# PCB_ManufactureDiagram.net
KiCad netlist of a schematic drawn in Altium Designer
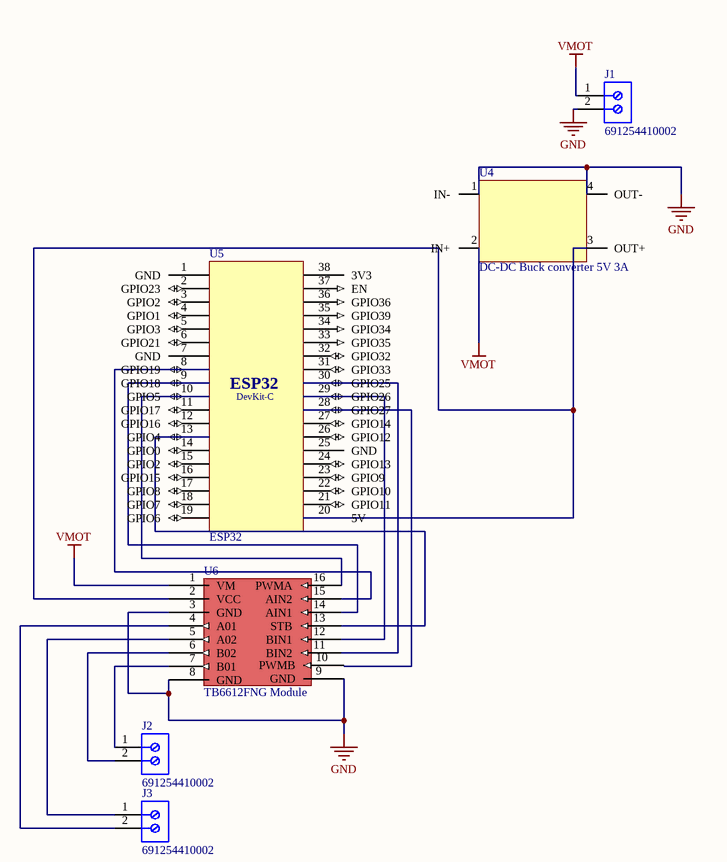
[diagram p0: PCB_ManufactureDiagram.SchDoc]

(export (version "E")
  (design (tool "Eeschema 10.0.6"))
  (components
    (comp (ref "J1")
      (value "691254410002")
      (footprint "691254410002")
      (description "Terminal Block, 7.62MM Pitch, Horizontal, Dual Pin, 12-30 AWG, 2 Pin")
      (libsource (lib "Altium Content Vault") (part "TBL - 1R - 02P - Screw"))
    )
    (comp (ref "J2")
      (value "691254410002")
      (footprint "691254410002")
      (description "Terminal Block, 7.62MM Pitch, Horizontal, Dual Pin, 12-30 AWG, 2 Pin")
      (libsource (lib "Altium Content Vault") (part "TBL - 1R - 02P - Screw"))
    )
    (comp (ref "J3")
      (value "691254410002")
      (footprint "691254410002")
      (description "Terminal Block, 7.62MM Pitch, Horizontal, Dual Pin, 12-30 AWG, 2 Pin")
      (libsource (lib "Altium Content Vault") (part "TBL - 1R - 02P - Screw"))
    )
    (comp (ref "U4")
      (value "DC-DC Buck converter 5V 3A")
      (footprint "DC-DC Buck converter 5V 3A")
      (description "MP1584 Series 28 V 3 A 1.5 MHz SMT Step-Down Converter - SOIC-8E")
      (fields
        (field (name "MANUFACTURER") "Monolithic Power Systems")
        (field (name "MANUFACTURER PART NUMBER") "MP1584EN-LF-Z")
      )
      (libsource (lib "DigiKey") (part "DC-DC Buck converter 5V 3A"))
    )
    (comp (ref "U5")
      (value "ESP32")
      (footprint "ESP32_DevKitCWROOM32")
      (description "Multiprotocol Modules SMD Module ESP32-WROOM-32E, ESP32-D0WD-V3, 16 MB SPI flash, PCB antenna")
      (fields
        (field (name "MANUFACTURER") "Espressif Systems")
        (field (name "MANUFACTURER PART NUMBER") "ESP32-WROOM-32E-N16")
      )
      (libsource (lib "EspressifSystems") (part "ESP32-WROOM32"))
    )
    (comp (ref "U6")
      (value "TB6612FNG Module")
      (footprint "TB6612FNG")
      (description "TB6612FNG Motion Motor Control Add-On Board")
      (fields (field (name "MANUFACTURER") "SparkFun") (field (name "MANUFACTURER PART NUMBER") "ROB-14451"))
      (libsource (lib "SparkfunElectronics") (part "TB6612FNG"))
    )
  )
  (nets
    (net (code "1") (name "GND") (class "Default")
      (node (ref "J1") (pin "2") (pinfunction "2_2") (pintype "passive"))
      (node (ref "U4") (pin "1") (pinfunction "IN-_1") (pintype "power_in"))
      (node (ref "U4") (pin "4") (pinfunction "OUT-_4") (pintype "power_in"))
      (node (ref "U6") (pin "3") (pinfunction "GND_3") (pintype "power_in"))
      (node (ref "U6") (pin "8") (pinfunction "GND_8") (pintype "power_in"))
      (node (ref "U6") (pin "9") (pinfunction "GND_9") (pintype "power_in"))
    )
    (net (code "2") (name "Net-(U4-OUT+)") (class "Default")
      (node (ref "U4") (pin "3") (pinfunction "OUT+_3") (pintype "power_in"))
      (node (ref "U5") (pin "20") (pinfunction "5V_20") (pintype "power_in"))
      (node (ref "U6") (pin "2") (pinfunction "VCC_2") (pintype "power_in"))
    )
    (net (code "3") (name "Net-(U5-GPIO4)") (class "Default")
      (node (ref "U5") (pin "13") (pinfunction "GPIO4_13") (pintype "bidirectional"))
      (node (ref "U6") (pin "13") (pinfunction "STB_13") (pintype "input"))
    )
    (net (code "4") (name "Net-(U5-GPIO5)") (class "Default")
      (node (ref "U5") (pin "10") (pinfunction "GPIO5_10") (pintype "bidirectional"))
      (node (ref "U6") (pin "16") (pinfunction "PWMA_16") (pintype "input"))
    )
    (net (code "5") (name "Net-(U5-GPIO18)") (class "Default")
      (node (ref "U5") (pin "9") (pinfunction "GPIO18_9") (pintype "bidirectional"))
      (node (ref "U6") (pin "14") (pinfunction "AIN1_14") (pintype "input"))
    )
    (net (code "6") (name "Net-(U5-GPIO19)") (class "Default")
      (node (ref "U5") (pin "8") (pinfunction "GPIO19_8") (pintype "bidirectional"))
      (node (ref "U6") (pin "15") (pinfunction "AIN2_15") (pintype "input"))
    )
    (net (code "7") (name "Net-(U5-GPIO25)") (class "Default")
      (node (ref "U5") (pin "30") (pinfunction "GPIO25_30") (pintype "bidirectional"))
      (node (ref "U6") (pin "11") (pinfunction "BIN2_11") (pintype "input"))
    )
    (net (code "8") (name "Net-(U5-GPIO26)") (class "Default")
      (node (ref "U5") (pin "29") (pinfunction "GPIO26_29") (pintype "bidirectional"))
      (node (ref "U6") (pin "12") (pinfunction "BIN1_12") (pintype "input"))
    )
    (net (code "9") (name "Net-(U6-A01)") (class "Default")
      (node (ref "J3") (pin "2") (pinfunction "2_2") (pintype "passive"))
      (node (ref "U6") (pin "4") (pinfunction "A01_4") (pintype "output"))
    )
    (net (code "10") (name "Net-(U6-A02)") (class "Default")
      (node (ref "J3") (pin "1") (pinfunction "1_1") (pintype "passive"))
      (node (ref "U6") (pin "5") (pinfunction "A02_5") (pintype "output"))
    )
    (net (code "11") (name "Net-(U6-B01)") (class "Default")
      (node (ref "J2") (pin "1") (pinfunction "1_1") (pintype "passive"))
      (node (ref "U6") (pin "7") (pinfunction "B01_7") (pintype "output"))
    )
    (net (code "12") (name "Net-(U6-B02)") (class "Default")
      (node (ref "J2") (pin "2") (pinfunction "2_2") (pintype "passive"))
      (node (ref "U6") (pin "6") (pinfunction "B02_6") (pintype "output"))
    )
    (net (code "13") (name "VMOT") (class "Default")
      (node (ref "J1") (pin "1") (pinfunction "1_1") (pintype "passive"))
      (node (ref "U4") (pin "2") (pinfunction "IN+_2") (pintype "power_in"))
      (node (ref "U6") (pin "1") (pinfunction "VM_1") (pintype "power_in"))
    )
    (net (code "14") (name "unconnected-(U5-3V3-Pad38)") (class "Default")
      (node (ref "U5") (pin "38") (pinfunction "3V3_38") (pintype "power_in"))
    )
    (net (code "15") (name "unconnected-(U5-EN-Pad37)") (class "Default")
      (node (ref "U5") (pin "37") (pinfunction "EN_37") (pintype "input"))
    )
    (net (code "16") (name "unconnected-(U5-GND-Pad1)") (class "Default")
      (node (ref "U5") (pin "1") (pinfunction "GND_1") (pintype "power_in"))
    )
    (net (code "17") (name "unconnected-(U5-GND-Pad7)") (class "Default")
      (node (ref "U5") (pin "7") (pinfunction "GND_7") (pintype "power_in"))
    )
    (net (code "18") (name "unconnected-(U5-GND-Pad25)") (class "Default")
      (node (ref "U5") (pin "25") (pinfunction "GND_25") (pintype "power_in"))
    )
    (net (code "19") (name "unconnected-(U5-GPIO0-Pad14)") (class "Default")
      (node (ref "U5") (pin "14") (pinfunction "GPIO0_14") (pintype "bidirectional"))
    )
    (net (code "20") (name "unconnected-(U5-GPIO1-Pad4)") (class "Default")
      (node (ref "U5") (pin "4") (pinfunction "GPIO1_4") (pintype "bidirectional"))
    )
    (net (code "21") (name "unconnected-(U5-GPIO2-Pad3)") (class "Default")
      (node (ref "U5") (pin "3") (pinfunction "GPIO2_3") (pintype "bidirectional"))
    )
    (net (code "22") (name "unconnected-(U5-GPIO2-Pad15)") (class "Default")
      (node (ref "U5") (pin "15") (pinfunction "GPIO2_15") (pintype "bidirectional"))
    )
    (net (code "23") (name "unconnected-(U5-GPIO3-Pad5)") (class "Default")
      (node (ref "U5") (pin "5") (pinfunction "GPIO3_5") (pintype "bidirectional"))
    )
    (net (code "24") (name "unconnected-(U5-GPIO6-Pad19)") (class "Default")
      (node (ref "U5") (pin "19") (pinfunction "GPIO6_19") (pintype "bidirectional"))
    )
    (net (code "25") (name "unconnected-(U5-GPIO7-Pad18)") (class "Default")
      (node (ref "U5") (pin "18") (pinfunction "GPIO7_18") (pintype "bidirectional"))
    )
    (net (code "26") (name "unconnected-(U5-GPIO8-Pad17)") (class "Default")
      (node (ref "U5") (pin "17") (pinfunction "GPIO8_17") (pintype "bidirectional"))
    )
    (net (code "27") (name "unconnected-(U5-GPIO9-Pad23)") (class "Default")
      (node (ref "U5") (pin "23") (pinfunction "GPIO9_23") (pintype "bidirectional"))
    )
    (net (code "28") (name "unconnected-(U5-GPIO10-Pad22)") (class "Default")
      (node (ref "U5") (pin "22") (pinfunction "GPIO10_22") (pintype "bidirectional"))
    )
    (net (code "29") (name "unconnected-(U5-GPIO11-Pad21)") (class "Default")
      (node (ref "U5") (pin "21") (pinfunction "GPIO11_21") (pintype "bidirectional"))
    )
    (net (code "30") (name "unconnected-(U5-GPIO12-Pad26)") (class "Default")
      (node (ref "U5") (pin "26") (pinfunction "GPIO12_26") (pintype "bidirectional"))
    )
    (net (code "31") (name "unconnected-(U5-GPIO13-Pad24)") (class "Default")
      (node (ref "U5") (pin "24") (pinfunction "GPIO13_24") (pintype "bidirectional"))
    )
    (net (code "32") (name "unconnected-(U5-GPIO14-Pad27)") (class "Default")
      (node (ref "U5") (pin "27") (pinfunction "GPIO14_27") (pintype "bidirectional"))
    )
    (net (code "33") (name "unconnected-(U5-GPIO15-Pad16)") (class "Default")
      (node (ref "U5") (pin "16") (pinfunction "GPIO15_16") (pintype "bidirectional"))
    )
    (net (code "34") (name "unconnected-(U5-GPIO16-Pad12)") (class "Default")
      (node (ref "U5") (pin "12") (pinfunction "GPIO16_12") (pintype "bidirectional"))
    )
    (net (code "35") (name "unconnected-(U5-GPIO17-Pad11)") (class "Default")
      (node (ref "U5") (pin "11") (pinfunction "GPIO17_11") (pintype "bidirectional"))
    )
    (net (code "36") (name "unconnected-(U5-GPIO21-Pad6)") (class "Default")
      (node (ref "U5") (pin "6") (pinfunction "GPIO21_6") (pintype "bidirectional"))
    )
    (net (code "37") (name "unconnected-(U5-GPIO23-Pad2)") (class "Default")
      (node (ref "U5") (pin "2") (pinfunction "GPIO23_2") (pintype "bidirectional"))
    )
    (net (code "38") (name "unconnected-(U5-GPIO27-Pad28)") (class "Default")
      (node (ref "U5") (pin "28") (pinfunction "GPIO27_28") (pintype "bidirectional"))
    )
    (net (code "39") (name "unconnected-(U5-GPIO32-Pad32)") (class "Default")
      (node (ref "U5") (pin "32") (pinfunction "GPIO32_32") (pintype "bidirectional"))
    )
    (net (code "40") (name "unconnected-(U5-GPIO33-Pad31)") (class "Default")
      (node (ref "U5") (pin "31") (pinfunction "GPIO33_31") (pintype "bidirectional"))
    )
    (net (code "41") (name "unconnected-(U5-GPIO34-Pad34)") (class "Default")
      (node (ref "U5") (pin "34") (pinfunction "GPIO34_34") (pintype "input"))
    )
    (net (code "42") (name "unconnected-(U5-GPIO35-Pad33)") (class "Default")
      (node (ref "U5") (pin "33") (pinfunction "GPIO35_33") (pintype "input"))
    )
    (net (code "43") (name "unconnected-(U5-GPIO36-Pad36)") (class "Default")
      (node (ref "U5") (pin "36") (pinfunction "GPIO36_36") (pintype "input"))
    )
    (net (code "44") (name "unconnected-(U5-GPIO39-Pad35)") (class "Default")
      (node (ref "U5") (pin "35") (pinfunction "GPIO39_35") (pintype "input"))
    )
    (net (code "45") (name "unconnected-(U6-PWMB-Pad10)") (class "Default")
      (node (ref "U6") (pin "10") (pinfunction "PWMB_10") (pintype "input"))
    )
  )
)
